# Power.net
KiCad netlist of a schematic drawn in Altium Designer
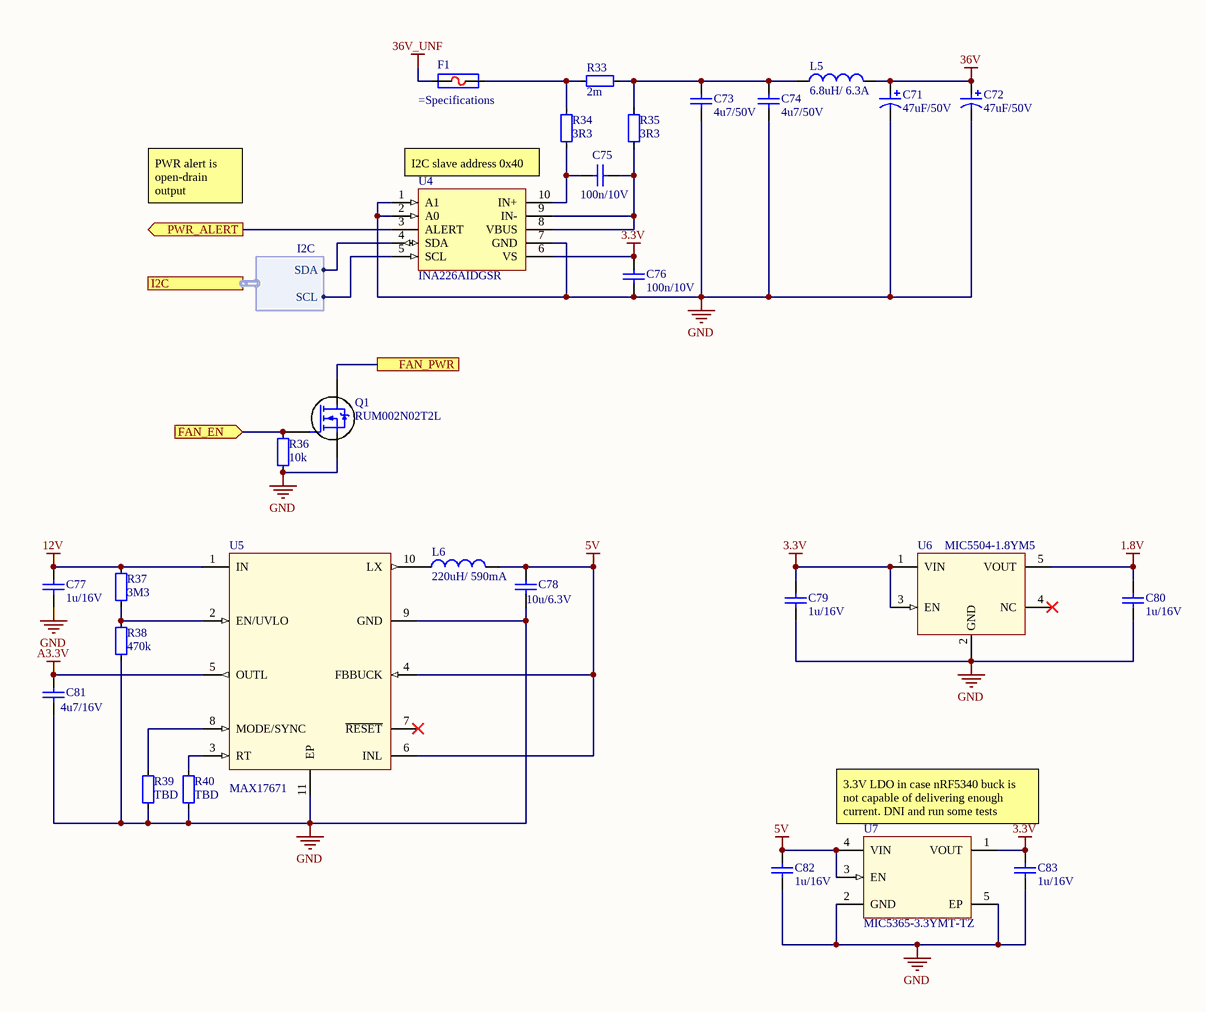
[diagram p0: Power.SchDoc]

(export (version "E")
  (design (tool "Eeschema 10.0.6"))
  (components
    (comp (ref "C71")
      (value "47uF/50V")
      (footprint "WURTH-L6.5-D8")
      (description "Aluminium Electrolytic Capacitors - SMD WCAP-ASLI 50V 47uF 20% ESR=690mOhms")
      (fields (field (name "VOLTAGE") "50V") (field (name "TOLERANCE") "20%"))
      (libsource (lib "dk_electrolytic_caps") (part "Wurth-47uF-50V-L6.5-D8"))
    )
    (comp (ref "C72")
      (value "47uF/50V")
      (footprint "WURTH-L6.5-D8")
      (description "Aluminium Electrolytic Capacitors - SMD WCAP-ASLI 50V 47uF 20% ESR=690mOhms")
      (fields (field (name "VOLTAGE") "50V") (field (name "TOLERANCE") "20%"))
      (libsource (lib "dk_electrolytic_caps") (part "Wurth-47uF-50V-L6.5-D8"))
    )
    (comp (ref "C73")
      (value "4u7/50V")
      (footprint "C1210")
      (fields (field (name "VOLTAGE") "50V") (field (name "TOLERANCE") "10%"))
      (libsource (lib "dk_capacitors") (part "4u7 50V X7R 1210"))
    )
    (comp (ref "C74")
      (value "4u7/50V")
      (footprint "C1210")
      (fields (field (name "VOLTAGE") "50V") (field (name "TOLERANCE") "10%"))
      (libsource (lib "dk_capacitors") (part "4u7 50V X7R 1210"))
    )
    (comp (ref "C75")
      (value "100n/10V")
      (footprint "C0402")
      (fields (field (name "VOLTAGE") "10V") (field (name "TOLERANCE") "20%"))
      (libsource (lib "dk_capacitors") (part "100n 10V X5R 0402"))
    )
    (comp (ref "C76")
      (value "100n/10V")
      (footprint "C0402")
      (fields (field (name "VOLTAGE") "10V") (field (name "TOLERANCE") "20%"))
      (libsource (lib "dk_capacitors") (part "100n 10V X5R 0402"))
    )
    (comp (ref "C77")
      (value "1u/16V")
      (footprint "C0603")
      (fields (field (name "VOLTAGE") "16V") (field (name "TOLERANCE") "10%"))
      (libsource (lib "dk_capacitors") (part "1u 16V X7R 0603"))
    )
    (comp (ref "C78")
      (value "10u/6.3V")
      (footprint "C0805")
      (fields (field (name "VOLTAGE") "6.3V") (field (name "TOLERANCE") "10%"))
      (libsource (lib "dk_capacitors") (part "10u 6V3 X7R 0805"))
    )
    (comp (ref "C79")
      (value "1u/16V")
      (footprint "C0603")
      (fields (field (name "VOLTAGE") "16V") (field (name "TOLERANCE") "10%"))
      (libsource (lib "dk_capacitors") (part "1u 16V X7R 0603"))
    )
    (comp (ref "C80")
      (value "1u/16V")
      (footprint "C0603")
      (fields (field (name "VOLTAGE") "16V") (field (name "TOLERANCE") "10%"))
      (libsource (lib "dk_capacitors") (part "1u 16V X7R 0603"))
    )
    (comp (ref "C81")
      (value "4u7/16V")
      (footprint "C0805")
      (fields (field (name "VOLTAGE") "16V") (field (name "TOLERANCE") "10%"))
      (libsource (lib "dk_capacitors") (part "4u7 16V X7R 0805"))
    )
    (comp (ref "C82")
      (value "1u/16V")
      (footprint "C0603")
      (fields (field (name "VOLTAGE") "16V") (field (name "TOLERANCE") "10%"))
      (libsource (lib "dk_capacitors") (part "1u 16V X7R 0603"))
    )
    (comp (ref "C83")
      (value "1u/16V")
      (footprint "C0603")
      (fields (field (name "VOLTAGE") "16V") (field (name "TOLERANCE") "10%"))
      (libsource (lib "dk_capacitors") (part "1u 16V X7R 0603"))
    )
    (comp (ref "F1")
      (value "~")
      (footprint "F2512")
      (description "Surface Mount Fuses 125VAC 5A .0125ohms 451 NANO2")
      (libsource (lib "dk_protection") (part "0451005.NRL"))
    )
    (comp (ref "L5")
      (value "6.8uH/ 6.3A")
      (footprint "SRR1260")
      (description "Fixed Inductors 6.8uH 30% SMD 1260")
      (fields (field (name "TOLERANCE") "30%") (field (name "MANUFACTURER PART NUMBER") "SRR1260-6R8Y"))
      (libsource (lib "dk_inductors") (part "SRR1260-6R8Y"))
    )
    (comp (ref "L6")
      (value "220uH/ 590mA")
      (footprint "TYS6045221M-10")
      (description "Fixed Inductors 220uH 20% -40C +125C")
      (fields (field (name "MANUFACTURER PART NUMBER") "TYS6045221M-10") (field (name "TOLERANCE") "20%"))
      (libsource (lib "dk_inductors") (part "TYS6045221M-10"))
    )
    (comp (ref "Q1")
      (value "RUM002N02T2L")
      (footprint "SOT-723-3")
      (description "N-Channel 20V 200mA (Ta) 150mW (Ta) Surface Mount VMT3")
      (libsource (lib "dk_transistors") (part "RUM002N02T2L"))
    )
    (comp (ref "R33")
      (value "2m")
      (footprint "R1206")
      (description "Current Sense Resistors - SMD 1W 0.002 OHMS 1%")
      (fields (field (name "TOLERANCE") "1%") (field (name "VOLTAGE") "100V"))
      (libsource (lib "dk_resistors") (part "2m 1W 100V 1206"))
    )
    (comp (ref "R34")
      (value "3R3")
      (footprint "R0402")
      (fields (field (name "TOLERANCE") "1%") (field (name "VOLTAGE") "50V"))
      (libsource (lib "dk_resistors") (part "3R3 100mW 50V 0402"))
    )
    (comp (ref "R35")
      (value "3R3")
      (footprint "R0402")
      (fields (field (name "TOLERANCE") "1%") (field (name "VOLTAGE") "50V"))
      (libsource (lib "dk_resistors") (part "3R3 100mW 50V 0402"))
    )
    (comp (ref "R36")
      (value "10k")
      (footprint "R0402")
      (fields (field (name "TOLERANCE") "1%") (field (name "VOLTAGE") "50V"))
      (libsource (lib "dk_resistors") (part "10k 63mW 50V 0402"))
    )
    (comp (ref "R37")
      (value "3M3")
      (footprint "R0402")
      (fields (field (name "TOLERANCE") "1%") (field (name "VOLTAGE") "50V"))
      (libsource (lib "dk_resistors") (part "3M3 63mW 50V 0402"))
    )
    (comp (ref "R38")
      (value "470k")
      (footprint "R0402")
      (fields (field (name "TOLERANCE") "1%") (field (name "VOLTAGE") "50V"))
      (libsource (lib "dk_resistors") (part "470k 63mW 50V 0402"))
    )
    (comp (ref "R39")
      (value "TBD")
      (footprint "R0402")
      (fields (field (name "TOLERANCE") "?%") (field (name "VOLTAGE") "?V"))
      (libsource (lib "dk_resistors") (part "R TBD 0402"))
    )
    (comp (ref "R40")
      (value "TBD")
      (footprint "R0402")
      (fields (field (name "TOLERANCE") "?%") (field (name "VOLTAGE") "?V"))
      (libsource (lib "dk_resistors") (part "R TBD 0402"))
    )
    (comp (ref "U4")
      (value "INA226AIDGSR")
      (footprint "MSOP-10")
      (description "Current & Power Monitors & Regulators Hi-Side Msmt,Bi-Dir Current/Pwr Mon")
      (libsource (lib "dk_ic_power") (part "INA226AIDGSR"))
    )
    (comp (ref "U5")
      (value "MAX17671")
      (footprint "TDFN-10")
      (description "Switching Voltage Regulators 4.5V - 60V, 150mA Synchronous DC-DC and 5V, 50mA low noise LDO")
      (fields (field (name "MANUFACTURER PART NUMBER") "MAX17671FATB+"))
      (libsource (lib "dk_ic_power") (part "MAX17671"))
    )
    (comp (ref "U6")
      (value "MIC5504-1.8YM5")
      (footprint "SOT23-5")
      (description "LDO Voltage Regulators Single 300mA LDO with Enable Pull-Down & Auto Discharge")
      (fields (field (name "MANUFACTURER PART NUMBER") "MIC5504-1.8YM5-TR"))
      (libsource (lib "dk_ic_power") (part "MIC5504-1.8YM5"))
    )
    (comp (ref "U7")
      (value "MIC5365-3.3YMT-TZ")
      (footprint "MLF-4")
      (description "LDO Voltage Regulators Ultra Small Single 150mA LDO")
      (libsource (lib "dk_ic_power") (part "MIC5365-3.3YMT-TZ"))
    )
  )
  (nets
    (net (code "2") (name "/FAN_EN") (class "Default")
      (node (ref "Q1") (pin "1") (pinfunction "G_1") (pintype "passive"))
      (node (ref "R36") (pin "2") (pinfunction "2_2") (pintype "passive"))
    )
    (net (code "3") (name "/FAN_PWR") (class "Default")
      (node (ref "Q1") (pin "3") (pinfunction "D_3") (pintype "passive"))
    )
    (net (code "4") (name "/PWR_ALERT") (class "Default")
      (node (ref "U4") (pin "3") (pinfunction "ALERT_3") (pintype "open_collector"))
    )
    (net (code "5") (name "/SCL") (class "Default")
      (node (ref "U4") (pin "5") (pinfunction "SCL_5") (pintype "input"))
    )
    (net (code "6") (name "/SDA") (class "Default")
      (node (ref "U4") (pin "4") (pinfunction "SDA_4") (pintype "bidirectional"))
    )
    (net (code "8") (name "1.8V") (class "Default")
      (node (ref "C80") (pin "2") (pinfunction "2_2") (pintype "passive"))
      (node (ref "U6") (pin "5") (pinfunction "VOUT_5") (pintype "power_in"))
    )
    (net (code "9") (name "3.3V") (class "Default")
      (node (ref "C76") (pin "2") (pinfunction "2_2") (pintype "passive"))
      (node (ref "C79") (pin "2") (pinfunction "2_2") (pintype "passive"))
      (node (ref "C83") (pin "2") (pinfunction "2_2") (pintype "passive"))
      (node (ref "U4") (pin "6") (pinfunction "VS_6") (pintype "power_in"))
      (node (ref "U6") (pin "1") (pinfunction "VIN_1") (pintype "power_in"))
      (node (ref "U6") (pin "3") (pinfunction "EN_3") (pintype "input"))
      (node (ref "U7") (pin "1") (pinfunction "VOUT_1") (pintype "power_in"))
    )
    (net (code "10") (name "5V") (class "Default")
      (node (ref "C78") (pin "2") (pinfunction "2_2") (pintype "passive"))
      (node (ref "C82") (pin "2") (pinfunction "2_2") (pintype "passive"))
      (node (ref "L6") (pin "2") (pinfunction "2_2") (pintype "passive"))
      (node (ref "U5") (pin "4") (pinfunction "FBBUCK_4") (pintype "input"))
      (node (ref "U5") (pin "6") (pinfunction "INL_6") (pintype "power_in"))
      (node (ref "U7") (pin "3") (pinfunction "EN_3") (pintype "input"))
      (node (ref "U7") (pin "4") (pinfunction "VIN_4") (pintype "power_in"))
    )
    (net (code "11") (name "12V") (class "Default")
      (node (ref "C77") (pin "2") (pinfunction "2_2") (pintype "passive"))
      (node (ref "R37") (pin "2") (pinfunction "2_2") (pintype "passive"))
      (node (ref "U5") (pin "1") (pinfunction "IN_1") (pintype "power_in"))
    )
    (net (code "12") (name "36V") (class "Default")
      (node (ref "C71") (pin "1") (pinfunction "1_1") (pintype "passive"))
      (node (ref "C72") (pin "1") (pinfunction "1_1") (pintype "passive"))
      (node (ref "L5") (pin "2") (pinfunction "2_2") (pintype "passive"))
    )
    (net (code "13") (name "36V_UNF") (class "Default") (node (ref "F1") (pin "1") (pintype "passive")))
    (net (code "14") (name "A3.3V") (class "Default")
      (node (ref "C81") (pin "2") (pinfunction "2_2") (pintype "passive"))
      (node (ref "U5") (pin "5") (pinfunction "OUTL_5") (pintype "output"))
    )
    (net (code "15") (name "GND") (class "Default")
      (node (ref "C71") (pin "2") (pinfunction "2_2") (pintype "passive"))
      (node (ref "C72") (pin "2") (pinfunction "2_2") (pintype "passive"))
      (node (ref "C73") (pin "1") (pinfunction "1_1") (pintype "passive"))
      (node (ref "C74") (pin "1") (pinfunction "1_1") (pintype "passive"))
      (node (ref "C76") (pin "1") (pinfunction "1_1") (pintype "passive"))
      (node (ref "C77") (pin "1") (pinfunction "1_1") (pintype "passive"))
      (node (ref "C78") (pin "1") (pinfunction "1_1") (pintype "passive"))
      (node (ref "C79") (pin "1") (pinfunction "1_1") (pintype "passive"))
      (node (ref "C80") (pin "1") (pinfunction "1_1") (pintype "passive"))
      (node (ref "C81") (pin "1") (pinfunction "1_1") (pintype "passive"))
      (node (ref "C82") (pin "1") (pinfunction "1_1") (pintype "passive"))
      (node (ref "C83") (pin "1") (pinfunction "1_1") (pintype "passive"))
      (node (ref "Q1") (pin "2") (pinfunction "S_2") (pintype "passive"))
      (node (ref "R36") (pin "1") (pinfunction "1_1") (pintype "passive"))
      (node (ref "R38") (pin "1") (pinfunction "1_1") (pintype "passive"))
      (node (ref "R39") (pin "1") (pinfunction "1_1") (pintype "passive"))
      (node (ref "R40") (pin "1") (pinfunction "1_1") (pintype "passive"))
      (node (ref "U4") (pin "1") (pinfunction "A1_1") (pintype "input"))
      (node (ref "U4") (pin "2") (pinfunction "A0_2") (pintype "input"))
      (node (ref "U4") (pin "7") (pinfunction "GND_7") (pintype "power_in"))
      (node (ref "U5") (pin "11") (pinfunction "EP_11") (pintype "power_in"))
      (node (ref "U5") (pin "9") (pinfunction "GND_9") (pintype "power_in"))
      (node (ref "U6") (pin "2") (pinfunction "GND_2") (pintype "power_in"))
      (node (ref "U7") (pin "2") (pinfunction "GND_2") (pintype "power_in"))
      (node (ref "U7") (pin "5") (pinfunction "EP_5") (pintype "power_in"))
    )
    (net (code "16") (name "Net-(C73-Pad2)") (class "Default")
      (node (ref "C73") (pin "2") (pinfunction "2_2") (pintype "passive"))
      (node (ref "C74") (pin "2") (pinfunction "2_2") (pintype "passive"))
      (node (ref "L5") (pin "1") (pinfunction "1_1") (pintype "passive"))
      (node (ref "R33") (pin "2") (pinfunction "2_2") (pintype "passive"))
      (node (ref "R35") (pin "2") (pinfunction "2_2") (pintype "passive"))
    )
    (net (code "17") (name "Net-(F1-Pad2)") (class "Default")
      (node (ref "F1") (pin "2") (pintype "passive"))
      (node (ref "R33") (pin "1") (pinfunction "1_1") (pintype "passive"))
      (node (ref "R34") (pin "2") (pinfunction "2_2") (pintype "passive"))
    )
    (net (code "18") (name "Net-(U4-IN+)") (class "Default")
      (node (ref "C75") (pin "1") (pinfunction "1_1") (pintype "passive"))
      (node (ref "R34") (pin "1") (pinfunction "1_1") (pintype "passive"))
      (node (ref "U4") (pin "10") (pinfunction "IN+_10") (pintype "passive"))
    )
    (net (code "19") (name "Net-(U4-IN-)") (class "Default")
      (node (ref "C75") (pin "2") (pinfunction "2_2") (pintype "passive"))
      (node (ref "R35") (pin "1") (pinfunction "1_1") (pintype "passive"))
      (node (ref "U4") (pin "8") (pinfunction "VBUS_8") (pintype "power_in"))
      (node (ref "U4") (pin "9") (pinfunction "IN-_9") (pintype "passive"))
    )
    (net (code "20") (name "Net-(U5-EN{slash}UVLO)") (class "Default")
      (node (ref "R37") (pin "1") (pinfunction "1_1") (pintype "passive"))
      (node (ref "R38") (pin "2") (pinfunction "2_2") (pintype "passive"))
      (node (ref "U5") (pin "2") (pinfunction "EN/UVLO_2") (pintype "input"))
    )
    (net (code "21") (name "Net-(U5-LX)") (class "Default")
      (node (ref "L6") (pin "1") (pinfunction "1_1") (pintype "passive"))
      (node (ref "U5") (pin "10") (pinfunction "LX_10") (pintype "output"))
    )
    (net (code "22") (name "Net-(U5-MODE{slash}SYNC)") (class "Default")
      (node (ref "R39") (pin "2") (pinfunction "2_2") (pintype "passive"))
      (node (ref "U5") (pin "8") (pinfunction "MODE/SYNC_8") (pintype "input"))
    )
    (net (code "23") (name "Net-(U5-RT)") (class "Default")
      (node (ref "R40") (pin "2") (pinfunction "2_2") (pintype "passive"))
      (node (ref "U5") (pin "3") (pinfunction "RT_3") (pintype "input"))
    )
    (net (code "24") (name "unconnected-(U5-~{RESET}-Pad7)") (class "Default")
      (node (ref "U5") (pin "7") (pinfunction "~{RESET}_7") (pintype "open_collector+no_connect"))
    )
    (net (code "25") (name "unconnected-(U6-NC-Pad4)") (class "Default")
      (node (ref "U6") (pin "4") (pinfunction "NC_4") (pintype "passive+no_connect"))
    )
  )
)
